# AltiumSchematicSheet.net
KiCad netlist of a schematic drawn in Altium Designer
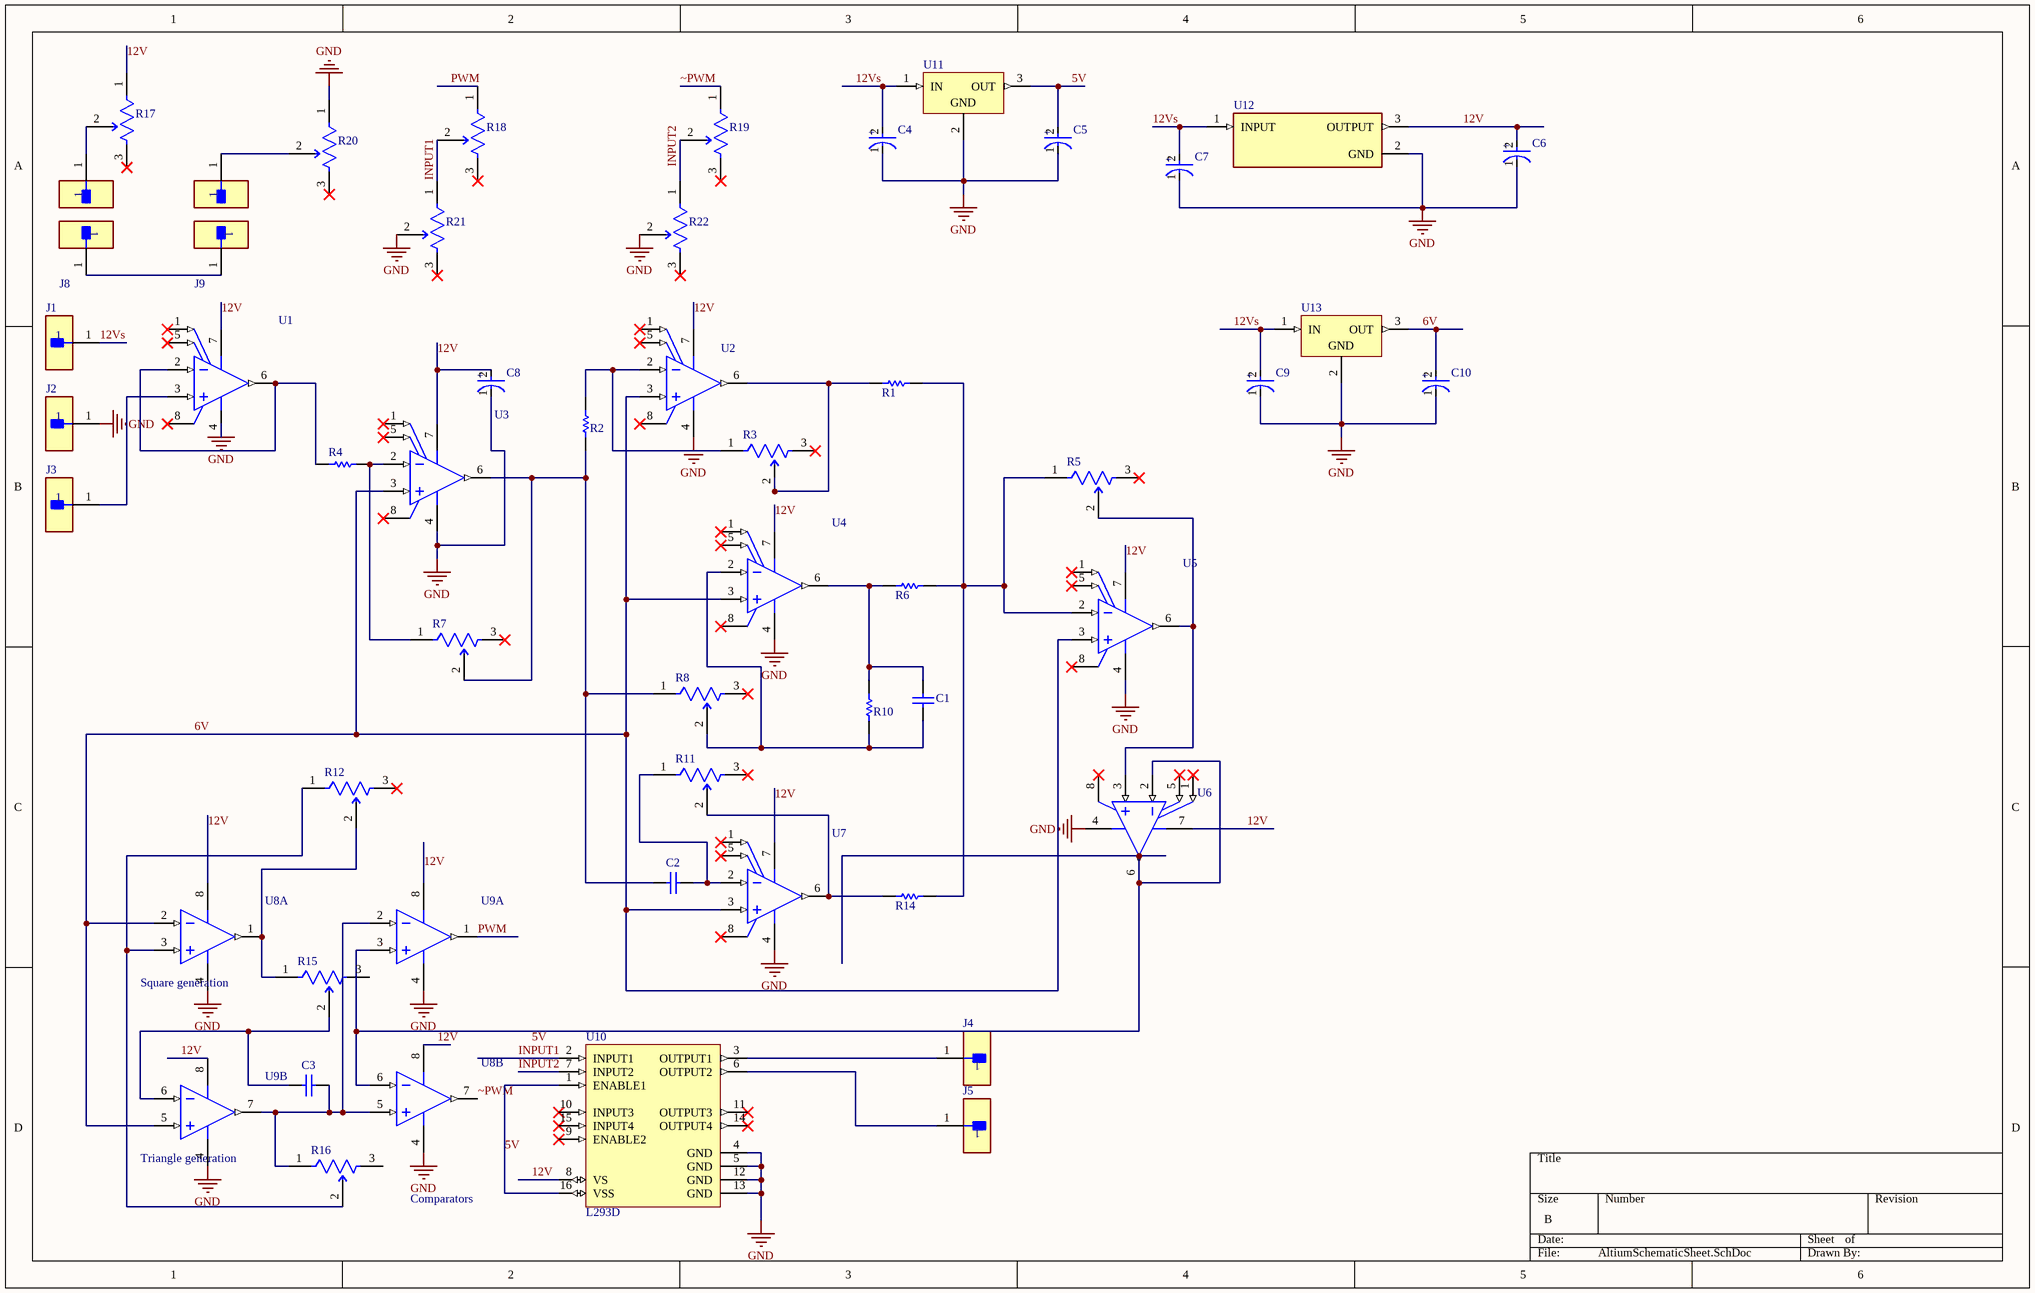
[diagram p0: AltiumSchematicSheet.SchDoc]

(export (version "E")
  (design (tool "Eeschema 10.0.6"))
  (components
    (comp (ref "C1")
      (value "C330C105M5U5TA")
      (footprint "KEMT-C330C105M5U5TA")
      (description "Ceramic Capacitor, 1 uF, +/- 20%, 50 V, -10 to 85 degC, 2-Pin THD, RoHS, Bulk")
      (fields (field (name "TOLERANCE") "±20%") (field (name "MANUFACTURER") "Kemet"))
      (libsource (lib "Altium Content Vault") (part "CAP-NP-2"))
    )
    (comp (ref "C2")
      (value "C330C105M5U5TA")
      (footprint "KEMT-C330C105M5U5TA")
      (description "Ceramic Capacitor, 1 uF, +/- 20%, 50 V, -10 to 85 degC, 2-Pin THD, RoHS, Bulk")
      (fields (field (name "TOLERANCE") "±20%") (field (name "MANUFACTURER") "Kemet"))
      (libsource (lib "Altium Content Vault") (part "CAP-NP-2"))
    )
    (comp (ref "C3")
      (value "C330C105M5U5TA")
      (footprint "KEMT-C330C105M5U5TA")
      (description "Ceramic Capacitor, 1 uF, +/- 20%, 50 V, -10 to 85 degC, 2-Pin THD, RoHS, Bulk")
      (fields (field (name "TOLERANCE") "±20%") (field (name "MANUFACTURER") "Kemet"))
      (libsource (lib "Altium Content Vault") (part "CAP-NP-2"))
    )
    (comp (ref "C4")
      (value "EEUFK1C472L")
      (footprint "FP-RAD-TH-D_12_5_0_5-L_40-MFG")
      (description "Aluminum Electrolytic Capacitors (Radial Lead Type) AEC-Q200 Qualified 4700uF ±20% 16V")
      (fields (field (name "VOLTAGE") "16V") (field (name "TOLERANCE") "20%"))
      (libsource (lib "Altium Content Vault") (part "203bc49f2ac43e59fd269a8c329ed05"))
    )
    (comp (ref "C5")
      (value "EEUFK1C472L")
      (footprint "FP-RAD-TH-D_12_5_0_5-L_40-MFG")
      (description "Aluminum Electrolytic Capacitors (Radial Lead Type) AEC-Q200 Qualified 4700uF ±20% 16V")
      (fields (field (name "VOLTAGE") "16V") (field (name "TOLERANCE") "20%"))
      (libsource (lib "Altium Content Vault") (part "203bc49f2ac43e59fd269a8c329ed05"))
    )
    (comp (ref "C6")
      (value "EEUFK1C472L")
      (footprint "FP-RAD-TH-D_12_5_0_5-L_40-MFG")
      (description "Aluminum Electrolytic Capacitors (Radial Lead Type) AEC-Q200 Qualified 4700uF ±20% 16V")
      (fields (field (name "VOLTAGE") "16V") (field (name "TOLERANCE") "20%"))
      (libsource (lib "Altium Content Vault") (part "203bc49f2ac43e59fd269a8c329ed05"))
    )
    (comp (ref "C7")
      (value "EEUFK1C472L")
      (footprint "FP-RAD-TH-D_12_5_0_5-L_40-MFG")
      (description "Aluminum Electrolytic Capacitors (Radial Lead Type) AEC-Q200 Qualified 4700uF ±20% 16V")
      (fields (field (name "VOLTAGE") "16V") (field (name "TOLERANCE") "20%"))
      (libsource (lib "Altium Content Vault") (part "203bc49f2ac43e59fd269a8c329ed05"))
    )
    (comp (ref "C8")
      (value "EEUFK1C472L")
      (footprint "FP-RAD-TH-D_12_5_0_5-L_40-MFG")
      (description "Aluminum Electrolytic Capacitors (Radial Lead Type) AEC-Q200 Qualified 4700uF ±20% 16V")
      (fields (field (name "VOLTAGE") "16V") (field (name "TOLERANCE") "20%"))
      (libsource (lib "Altium Content Vault") (part "203bc49f2ac43e59fd269a8c329ed05"))
    )
    (comp (ref "C9")
      (value "EEUFK1C472L")
      (footprint "FP-RAD-TH-D_12_5_0_5-L_40-MFG")
      (description "Aluminum Electrolytic Capacitors (Radial Lead Type) AEC-Q200 Qualified 4700uF ±20% 16V")
      (fields (field (name "VOLTAGE") "16V") (field (name "TOLERANCE") "20%"))
      (libsource (lib "Altium Content Vault") (part "203bc49f2ac43e59fd269a8c329ed05"))
    )
    (comp (ref "C10")
      (value "EEUFK1C472L")
      (footprint "FP-RAD-TH-D_12_5_0_5-L_40-MFG")
      (description "Aluminum Electrolytic Capacitors (Radial Lead Type) AEC-Q200 Qualified 4700uF ±20% 16V")
      (fields (field (name "VOLTAGE") "16V") (field (name "TOLERANCE") "20%"))
      (libsource (lib "Altium Content Vault") (part "203bc49f2ac43e59fd269a8c329ed05"))
    )
    (comp (ref "J1")
      (value "PBC01SAAN")
      (footprint "FP-PBC01SAAN-MFG")
      (description "CONN HEADER VERT 1POS")
      (libsource (lib "Altium Content Vault") (part "dd45045ce8184df9e99e12baf3f412c"))
    )
    (comp (ref "J2")
      (value "PBC01SAAN")
      (footprint "FP-PBC01SAAN-MFG")
      (description "CONN HEADER VERT 1POS")
      (libsource (lib "Altium Content Vault") (part "dd45045ce8184df9e99e12baf3f412c"))
    )
    (comp (ref "J3")
      (value "PBC01SAAN")
      (footprint "FP-PBC01SAAN-MFG")
      (description "CONN HEADER VERT 1POS")
      (libsource (lib "Altium Content Vault") (part "dd45045ce8184df9e99e12baf3f412c"))
    )
    (comp (ref "J4")
      (value "PBC01SAAN")
      (footprint "FP-PBC01SAAN-MFG")
      (description "CONN HEADER VERT 1POS")
      (libsource (lib "") (part "dd45045ce8184df9e99e12baf3f412c_2"))
    )
    (comp (ref "J5")
      (value "PBC01SAAN")
      (footprint "FP-PBC01SAAN-MFG")
      (description "CONN HEADER VERT 1POS")
      (libsource (lib "") (part "dd45045ce8184df9e99e12baf3f412c_2"))
    )
    (comp (ref "J6")
      (value "PBC01SAAN")
      (footprint "FP-PBC01SAAN-MFG")
      (description "CONN HEADER VERT 1POS")
      (libsource (lib "") (part "dd45045ce8184df9e99e12baf3f412c_1"))
    )
    (comp (ref "J7")
      (value "PBC01SAAN")
      (footprint "FP-PBC01SAAN-MFG")
      (description "CONN HEADER VERT 1POS")
      (libsource (lib "") (part "dd45045ce8184df9e99e12baf3f412c_1"))
    )
    (comp (ref "J8")
      (value "PBC01SAAN")
      (footprint "FP-PBC01SAAN-MFG")
      (description "CONN HEADER VERT 1POS")
      (libsource (lib "") (part "dd45045ce8184df9e99e12baf3f412c_3"))
    )
    (comp (ref "J9")
      (value "PBC01SAAN")
      (footprint "FP-PBC01SAAN-MFG")
      (description "CONN HEADER VERT 1POS")
      (libsource (lib "") (part "dd45045ce8184df9e99e12baf3f412c_3"))
    )
    (comp (ref "R1")
      (value "MFR-25FBF52-47K5")
      (footprint "RESA60-630X240")
      (description "Axial Resistor, 47.5 KOhm, +/- 1%, 0.25 W, -55 to 155 degC, 2-Pin THD, RoHS, Bulk")
      (fields (field (name "TOLERANCE") "20%"))
      (libsource (lib "Altium Content Vault") (part "RES-2"))
    )
    (comp (ref "R2")
      (value "MFR-25FBF52-47K5")
      (footprint "RESA60-630X240")
      (description "Axial Resistor, 47.5 KOhm, +/- 1%, 0.25 W, -55 to 155 degC, 2-Pin THD, RoHS, Bulk")
      (fields (field (name "TOLERANCE") "20%"))
      (libsource (lib "Altium Content Vault") (part "RES-2"))
    )
    (comp (ref "R3")
      (value "3296W-1-501LF")
      (footprint "FP-3296W-MFG")
      (description "TRIMMER 500 OHM 0.5W PC PIN TOP")
      (fields (field (name "TOLERANCE") "10%"))
      (libsource (lib "Altium Content Vault") (part "2dcfd2547301a7d3209a5e99acfd772"))
    )
    (comp (ref "R4")
      (value "MFR-25FBF52-47K5")
      (footprint "RESA60-630X240")
      (description "Axial Resistor, 47.5 KOhm, +/- 1%, 0.25 W, -55 to 155 degC, 2-Pin THD, RoHS, Bulk")
      (fields (field (name "TOLERANCE") "20%"))
      (libsource (lib "Altium Content Vault") (part "RES-2"))
    )
    (comp (ref "R5")
      (value "3296W-1-501LF")
      (footprint "FP-3296W-MFG")
      (description "TRIMMER 500 OHM 0.5W PC PIN TOP")
      (fields (field (name "TOLERANCE") "10%"))
      (libsource (lib "Altium Content Vault") (part "2dcfd2547301a7d3209a5e99acfd772"))
    )
    (comp (ref "R6")
      (value "MFR-25FBF52-47K5")
      (footprint "RESA60-630X240")
      (description "Axial Resistor, 47.5 KOhm, +/- 1%, 0.25 W, -55 to 155 degC, 2-Pin THD, RoHS, Bulk")
      (fields (field (name "TOLERANCE") "20%"))
      (libsource (lib "Altium Content Vault") (part "RES-2"))
    )
    (comp (ref "R7")
      (value "3296W-1-501LF")
      (footprint "FP-3296W-MFG")
      (description "TRIMMER 500 OHM 0.5W PC PIN TOP")
      (fields (field (name "TOLERANCE") "10%"))
      (libsource (lib "Altium Content Vault") (part "2dcfd2547301a7d3209a5e99acfd772"))
    )
    (comp (ref "R8")
      (value "3296W-1-501LF")
      (footprint "FP-3296W-MFG")
      (description "TRIMMER 500 OHM 0.5W PC PIN TOP")
      (fields (field (name "TOLERANCE") "10%"))
      (libsource (lib "Altium Content Vault") (part "2dcfd2547301a7d3209a5e99acfd772"))
    )
    (comp (ref "R10")
      (value "MFR-25FBF52-47K5")
      (footprint "RESA60-630X240")
      (description "Axial Resistor, 47.5 KOhm, +/- 1%, 0.25 W, -55 to 155 degC, 2-Pin THD, RoHS, Bulk")
      (fields (field (name "TOLERANCE") "20%"))
      (libsource (lib "Altium Content Vault") (part "RES-2"))
    )
    (comp (ref "R11")
      (value "3296W-1-501LF")
      (footprint "FP-3296W-MFG")
      (description "TRIMMER 500 OHM 0.5W PC PIN TOP")
      (fields (field (name "TOLERANCE") "10%"))
      (libsource (lib "Altium Content Vault") (part "2dcfd2547301a7d3209a5e99acfd772"))
    )
    (comp (ref "R12")
      (value "3296W-1-501LF")
      (footprint "FP-3296W-MFG")
      (description "TRIMMER 500 OHM 0.5W PC PIN TOP")
      (fields (field (name "TOLERANCE") "10%"))
      (libsource (lib "Altium Content Vault") (part "2dcfd2547301a7d3209a5e99acfd772"))
    )
    (comp (ref "R14")
      (value "MFR-25FBF52-47K5")
      (footprint "RESA60-630X240")
      (description "Axial Resistor, 47.5 KOhm, +/- 1%, 0.25 W, -55 to 155 degC, 2-Pin THD, RoHS, Bulk")
      (fields (field (name "TOLERANCE") "20%"))
      (libsource (lib "Altium Content Vault") (part "RES-2"))
    )
    (comp (ref "R15")
      (value "3296W-1-501LF")
      (footprint "FP-3296W-MFG")
      (description "TRIMMER 500 OHM 0.5W PC PIN TOP")
      (fields (field (name "TOLERANCE") "10%"))
      (libsource (lib "Altium Content Vault") (part "2dcfd2547301a7d3209a5e99acfd772"))
    )
    (comp (ref "R16")
      (value "3296W-1-501LF")
      (footprint "FP-3296W-MFG")
      (description "TRIMMER 500 OHM 0.5W PC PIN TOP")
      (fields (field (name "TOLERANCE") "10%"))
      (libsource (lib "Altium Content Vault") (part "2dcfd2547301a7d3209a5e99acfd772"))
    )
    (comp (ref "R17")
      (value "3296W-1-501LF")
      (footprint "FP-3296W-MFG")
      (description "TRIMMER 500 OHM 0.5W PC PIN TOP")
      (fields (field (name "TOLERANCE") "10%"))
      (libsource (lib "Altium Content Vault") (part "2dcfd2547301a7d3209a5e99acfd772"))
    )
    (comp (ref "R18")
      (value "3296W-1-501LF")
      (footprint "FP-3296W-MFG")
      (description "TRIMMER 500 OHM 0.5W PC PIN TOP")
      (fields (field (name "TOLERANCE") "10%"))
      (libsource (lib "Altium Content Vault") (part "2dcfd2547301a7d3209a5e99acfd772"))
    )
    (comp (ref "R19")
      (value "3296W-1-501LF")
      (footprint "FP-3296W-MFG")
      (description "TRIMMER 500 OHM 0.5W PC PIN TOP")
      (fields (field (name "TOLERANCE") "10%"))
      (libsource (lib "Altium Content Vault") (part "2dcfd2547301a7d3209a5e99acfd772"))
    )
    (comp (ref "R20")
      (value "3296W-1-501LF")
      (footprint "FP-3296W-MFG")
      (description "TRIMMER 500 OHM 0.5W PC PIN TOP")
      (fields (field (name "TOLERANCE") "10%"))
      (libsource (lib "Altium Content Vault") (part "2dcfd2547301a7d3209a5e99acfd772"))
    )
    (comp (ref "R21")
      (value "3296W-1-501LF")
      (footprint "FP-3296W-MFG")
      (description "TRIMMER 500 OHM 0.5W PC PIN TOP")
      (fields (field (name "TOLERANCE") "10%"))
      (libsource (lib "Altium Content Vault") (part "2dcfd2547301a7d3209a5e99acfd772"))
    )
    (comp (ref "R22")
      (value "3296W-1-501LF")
      (footprint "FP-3296W-MFG")
      (description "TRIMMER 500 OHM 0.5W PC PIN TOP")
      (fields (field (name "TOLERANCE") "10%"))
      (libsource (lib "Altium Content Vault") (part "2dcfd2547301a7d3209a5e99acfd772"))
    )
    (comp (ref "U1")
      (value "UA741CP")
      (footprint "P0008A")
      (description "General-Purpose Operational Amplifier, 7 to 36 V, 0 to 70 degC, 8-pin DIP (P8), Pb-Free (RoHS)")
      (fields (field (name "MANUFACTURER") "Texas Instruments"))
      (libsource (lib "Altium Content Vault") (part "TI-AMP-S5-2-8"))
    )
    (comp (ref "U2")
      (value "UA741CP")
      (footprint "P0008A")
      (description "General-Purpose Operational Amplifier, 7 to 36 V, 0 to 70 degC, 8-pin DIP (P8), Pb-Free (RoHS)")
      (fields (field (name "MANUFACTURER") "Texas Instruments"))
      (libsource (lib "Altium Content Vault") (part "TI-AMP-S5-2-8"))
    )
    (comp (ref "U3")
      (value "UA741CP")
      (footprint "P0008A")
      (description "General-Purpose Operational Amplifier, 7 to 36 V, 0 to 70 degC, 8-pin DIP (P8), Pb-Free (RoHS)")
      (fields (field (name "MANUFACTURER") "Texas Instruments"))
      (libsource (lib "Altium Content Vault") (part "TI-AMP-S5-2-8"))
    )
    (comp (ref "U4")
      (value "UA741CP")
      (footprint "P0008A")
      (description "General-Purpose Operational Amplifier, 7 to 36 V, 0 to 70 degC, 8-pin DIP (P8), Pb-Free (RoHS)")
      (fields (field (name "MANUFACTURER") "Texas Instruments"))
      (libsource (lib "Altium Content Vault") (part "TI-AMP-S5-2-8"))
    )
    (comp (ref "U5")
      (value "UA741CP")
      (footprint "P0008A")
      (description "General-Purpose Operational Amplifier, 7 to 36 V, 0 to 70 degC, 8-pin DIP (P8), Pb-Free (RoHS)")
      (fields (field (name "MANUFACTURER") "Texas Instruments"))
      (libsource (lib "Altium Content Vault") (part "TI-AMP-S5-2-8"))
    )
    (comp (ref "U6")
      (value "UA741CP")
      (footprint "P0008A")
      (description "General-Purpose Operational Amplifier, 7 to 36 V, 0 to 70 degC, 8-pin DIP (P8), Pb-Free (RoHS)")
      (fields (field (name "MANUFACTURER") "Texas Instruments"))
      (libsource (lib "Altium Content Vault") (part "TI-AMP-S5-2-8"))
    )
    (comp (ref "U7")
      (value "UA741CP")
      (footprint "P0008A")
      (description "General-Purpose Operational Amplifier, 7 to 36 V, 0 to 70 degC, 8-pin DIP (P8), Pb-Free (RoHS)")
      (fields (field (name "MANUFACTURER") "Texas Instruments"))
      (libsource (lib "Altium Content Vault") (part "TI-AMP-S5-2-8"))
    )
    (comp (ref "U8")
      (value "TL072CP")
      (footprint "P0008A")
      (fields (field (name "MANUFACTURER") "Texas Instruments"))
      (libsource (lib "Altium Content Vault") (part "TI-AMP-D6-2-8_D"))
    )
    (comp (ref "U9")
      (value "TL072CP")
      (footprint "P0008A")
      (fields (field (name "MANUFACTURER") "Texas Instruments"))
      (libsource (lib "Altium Content Vault") (part "TI-AMP-D6-2-8_D"))
    )
    (comp (ref "U10")
      (value "L293D")
      (footprint "STM-L293D-16")
      (description "Push-Pull Four Channel Driver with Diode, 4.5 to 36 V, -40 to 150 degC, 16-Pin PDIP, RoHS, Tube")
      (fields (field (name "MANUFACTURER") "STMicroelectronics"))
      (libsource (lib "Altium Content Vault") (part "STM-L293D-16"))
    )
    (comp (ref "U11")
      (value "LM7805CT")
      (footprint "FAIR-TO-220-3")
      (description "Positive Voltage Regulator, 5 V, 1 A, -40 to 125 degC, 3-Pin TO-220, RoHS, Tube")
      (fields (field (name "MANUFACTURER") "FairchildSemiconductor"))
      (libsource (lib "Altium Content Vault") (part "FAIR-LM7805CT-TO220-3"))
    )
    (comp (ref "U12")
      (value "LM7812CT")
      (footprint "FP-TO220B03-MFG")
      (description "IC REG LINEAR 12V 1A TO220-3")
      (fields
        (field (name "OCTOPART") "https://octopart.com/lm7812ct-on+semiconductor-14383031")
        (field (name "OBSOLETE PART") "true")
      )
      (libsource (lib "Altium Content Vault") (part "6207a8f1a6b4db326a9e0a8a99b4969"))
    )
    (comp (ref "U13")
      (value "LM7805CT")
      (footprint "FAIR-TO-220-3")
      (description "Positive Voltage Regulator, 5 V, 1 A, -40 to 125 degC, 3-Pin TO-220, RoHS, Tube")
      (fields (field (name "MANUFACTURER") "FairchildSemiconductor"))
      (libsource (lib "Altium Content Vault") (part "FAIR-LM7805CT-TO220-3"))
    )
  )
  (nets
    (net (code "1") (name "/5V") (class "Default")
      (node (ref "C5") (pin "2") (pinfunction "A_2") (pintype "passive"))
      (node (ref "U10") (pin "1") (pinfunction "ENABLE1_1") (pintype "input"))
      (node (ref "U10") (pin "16") (pinfunction "VSS_16") (pintype "bidirectional"))
      (node (ref "U11") (pin "3") (pinfunction "OUT_3") (pintype "output"))
    )
    (net (code "2") (name "/6V") (class "Default")
      (node (ref "C10") (pin "2") (pinfunction "A_2") (pintype "passive"))
      (node (ref "U13") (pin "3") (pinfunction "OUT_3") (pintype "output"))
      (node (ref "U2") (pin "3") (pinfunction "IN+_3") (pintype "input"))
      (node (ref "U3") (pin "3") (pinfunction "IN+_3") (pintype "input"))
      (node (ref "U4") (pin "3") (pinfunction "IN+_3") (pintype "input"))
      (node (ref "U5") (pin "3") (pinfunction "IN+_3") (pintype "input"))
      (node (ref "U7") (pin "3") (pinfunction "IN+_3") (pintype "input"))
      (node (ref "U8") (pin "2") (pinfunction "IN1-_2") (pintype "input"))
      (node (ref "U9") (pin "5") (pinfunction "IN2+_5") (pintype "input"))
    )
    (net (code "3") (name "/12V") (class "Default")
      (node (ref "C6") (pin "2") (pinfunction "A_2") (pintype "passive"))
      (node (ref "C8") (pin "2") (pinfunction "A_2") (pintype "passive"))
      (node (ref "R17") (pin "1") (pinfunction "CCW_1") (pintype "passive"))
      (node (ref "U1") (pin "7") (pinfunction "VCC+_7") (pintype "power_in"))
      (node (ref "U10") (pin "8") (pinfunction "VS_8") (pintype "bidirectional"))
      (node (ref "U12") (pin "3") (pinfunction "OUTPUT_3") (pintype "output"))
      (node (ref "U2") (pin "7") (pinfunction "VCC+_7") (pintype "power_in"))
      (node (ref "U3") (pin "7") (pinfunction "VCC+_7") (pintype "power_in"))
      (node (ref "U4") (pin "7") (pinfunction "VCC+_7") (pintype "power_in"))
      (node (ref "U5") (pin "7") (pinfunction "VCC+_7") (pintype "power_in"))
      (node (ref "U6") (pin "7") (pinfunction "VCC+_7") (pintype "power_in"))
      (node (ref "U7") (pin "7") (pinfunction "VCC+_7") (pintype "power_in"))
      (node (ref "U8") (pin "8") (pinfunction "VCC+_8") (pintype "power_in"))
      (node (ref "U9") (pin "8") (pinfunction "VCC+_8") (pintype "power_in"))
    )
    (net (code "4") (name "/12Vs") (class "Default")
      (node (ref "C4") (pin "2") (pinfunction "A_2") (pintype "passive"))
      (node (ref "C7") (pin "2") (pinfunction "A_2") (pintype "passive"))
      (node (ref "C9") (pin "2") (pinfunction "A_2") (pintype "passive"))
      (node (ref "J1") (pin "1") (pinfunction "1_1") (pintype "passive"))
      (node (ref "U11") (pin "1") (pinfunction "IN_1") (pintype "input"))
      (node (ref "U12") (pin "1") (pinfunction "INPUT_1") (pintype "input"))
      (node (ref "U13") (pin "1") (pinfunction "IN_1") (pintype "input"))
    )
    (net (code "5") (name "/INPUT1") (class "Default")
      (node (ref "R18") (pin "2") (pinfunction "WIPER_2") (pintype "passive"))
      (node (ref "R21") (pin "1") (pinfunction "CCW_1") (pintype "passive"))
      (node (ref "U10") (pin "2") (pinfunction "INPUT1_2") (pintype "input"))
    )
    (net (code "6") (name "/INPUT2") (class "Default")
      (node (ref "R19") (pin "2") (pinfunction "WIPER_2") (pintype "passive"))
      (node (ref "R22") (pin "1") (pinfunction "CCW_1") (pintype "passive"))
      (node (ref "U10") (pin "7") (pinfunction "INPUT2_7") (pintype "input"))
    )
    (net (code "7") (name "/PWM") (class "Default")
      (node (ref "R18") (pin "1") (pinfunction "CCW_1") (pintype "passive"))
      (node (ref "U9") (pin "1") (pinfunction "OUT1_1") (pintype "output"))
    )
    (net (code "8") (name "/~PWM") (class "Default")
      (node (ref "R19") (pin "1") (pinfunction "CCW_1") (pintype "passive"))
      (node (ref "U8") (pin "7") (pinfunction "OUT2_7") (pintype "output"))
    )
    (net (code "9") (name "GND") (class "Default")
      (node (ref "C10") (pin "1") (pinfunction "C_1") (pintype "passive"))
      (node (ref "C4") (pin "1") (pinfunction "C_1") (pintype "passive"))
      (node (ref "C5") (pin "1") (pinfunction "C_1") (pintype "passive"))
      (node (ref "C6") (pin "1") (pinfunction "C_1") (pintype "passive"))
      (node (ref "C7") (pin "1") (pinfunction "C_1") (pintype "passive"))
      (node (ref "C8") (pin "1") (pinfunction "C_1") (pintype "passive"))
      (node (ref "C9") (pin "1") (pinfunction "C_1") (pintype "passive"))
      (node (ref "J2") (pin "1") (pinfunction "1_1") (pintype "passive"))
      (node (ref "R20") (pin "1") (pinfunction "CCW_1") (pintype "passive"))
      (node (ref "R21") (pin "2") (pinfunction "WIPER_2") (pintype "passive"))
      (node (ref "R22") (pin "2") (pinfunction "WIPER_2") (pintype "passive"))
      (node (ref "U1") (pin "4") (pinfunction "VCC-_4") (pintype "power_in"))
      (node (ref "U10") (pin "12") (pinfunction "GND_12") (pintype "power_in"))
      (node (ref "U10") (pin "13") (pinfunction "GND_13") (pintype "power_in"))
      (node (ref "U10") (pin "4") (pinfunction "GND_4") (pintype "power_in"))
      (node (ref "U10") (pin "5") (pinfunction "GND_5") (pintype "power_in"))
      (node (ref "U11") (pin "2") (pinfunction "GND_2") (pintype "power_in"))
      (node (ref "U12") (pin "2") (pinfunction "GND_2") (pintype "power_in"))
      (node (ref "U13") (pin "2") (pinfunction "GND_2") (pintype "power_in"))
      (node (ref "U2") (pin "4") (pinfunction "VCC-_4") (pintype "power_in"))
      (node (ref "U3") (pin "4") (pinfunction "VCC-_4") (pintype "power_in"))
      (node (ref "U4") (pin "4") (pinfunction "VCC-_4") (pintype "power_in"))
      (node (ref "U5") (pin "4") (pinfunction "VCC-_4") (pintype "power_in"))
      (node (ref "U6") (pin "4") (pinfunction "VCC-_4") (pintype "power_in"))
      (node (ref "U7") (pin "4") (pinfunction "VCC-_4") (pintype "power_in"))
      (node (ref "U8") (pin "4") (pinfunction "VCC-_4") (pintype "power_in"))
      (node (ref "U9") (pin "4") (pinfunction "VCC-_4") (pintype "power_in"))
    )
    (net (code "10") (name "Net-(J8-Pad1)") (class "Default")
      (node (ref "J8") (pin "1") (pinfunction "1_1") (pintype "passive"))
      (node (ref "J9") (pin "1") (pinfunction "1_1") (pintype "passive"))
    )
    (net (code "11") (name "Net-(R3-CCW)") (class "Default")
      (node (ref "R2") (pin "2") (pinfunction "2_2") (pintype "passive"))
      (node (ref "R3") (pin "1") (pinfunction "CCW_1") (pintype "passive"))
      (node (ref "U2") (pin "2") (pinfunction "IN-_2") (pintype "input"))
    )
    (net (code "12") (name "Net-(R3-WIPER)") (class "Default")
      (node (ref "R1") (pin "2") (pinfunction "2_2") (pintype "passive"))
      (node (ref "R3") (pin "2") (pinfunction "WIPER_2") (pintype "passive"))
      (node (ref "U2") (pin "6") (pinfunction "OUT_6") (pintype "output"))
    )
    (net (code "13") (name "Net-(R5-CCW)") (class "Default")
      (node (ref "R1") (pin "1") (pinfunction "1_1") (pintype "passive"))
      (node (ref "R14") (pin "1") (pinfunction "1_1") (pintype "passive"))
      (node (ref "R5") (pin "1") (pinfunction "CCW_1") (pintype "passive"))
      (node (ref "R6") (pin "1") (pinfunction "1_1") (pintype "passive"))
      (node (ref "U5") (pin "2") (pinfunction "IN-_2") (pintype "input"))
    )
    (net (code "14") (name "Net-(R5-WIPER)") (class "Default")
      (node (ref "R5") (pin "2") (pinfunction "WIPER_2") (pintype "passive"))
      (node (ref "U5") (pin "6") (pinfunction "OUT_6") (pintype "output"))
      (node (ref "U6") (pin "3") (pinfunction "IN+_3") (pintype "input"))
    )
    (net (code "15") (name "Net-(R7-CCW)") (class "Default")
      (node (ref "R4") (pin "2") (pinfunction "2_2") (pintype "passive"))
      (node (ref "R7") (pin "1") (pinfunction "CCW_1") (pintype "passive"))
      (node (ref "U3") (pin "2") (pinfunction "IN-_2") (pintype "input"))
    )
    (net (code "16") (name "Net-(R7-WIPER)") (class "Default")
      (node (ref "C2") (pin "2") (pinfunction "2_2") (pintype "passive"))
      (node (ref "R2") (pin "1") (pinfunction "1_1") (pintype "passive"))
      (node (ref "R7") (pin "2") (pinfunction "WIPER_2") (pintype "passive"))
      (node (ref "R8") (pin "1") (pinfunction "CCW_1") (pintype "passive"))
      (node (ref "U3") (pin "6") (pinfunction "OUT_6") (pintype "output"))
    )
    (net (code "17") (name "Net-(R8-WIPER)") (class "Default")
      (node (ref "C1") (pin "1") (pinfunction "1_1") (pintype "passive"))
      (node (ref "R10") (pin "1") (pinfunction "1_1") (pintype "passive"))
      (node (ref "R8") (pin "2") (pinfunction "WIPER_2") (pintype "passive"))
      (node (ref "U4") (pin "2") (pinfunction "IN-_2") (pintype "input"))
    )
    (net (code "18") (name "Net-(R11-CCW)") (class "Default")
      (node (ref "C2") (pin "1") (pinfunction "1_1") (pintype "passive"))
      (node (ref "R11") (pin "1") (pinfunction "CCW_1") (pintype "passive"))
      (node (ref "U7") (pin "2") (pinfunction "IN-_2") (pintype "input"))
    )
    (net (code "19") (name "Net-(R11-WIPER)") (class "Default")
      (node (ref "R11") (pin "2") (pinfunction "WIPER_2") (pintype "passive"))
      (node (ref "R14") (pin "2") (pinfunction "2_2") (pintype "passive"))
      (node (ref "U7") (pin "6") (pinfunction "OUT_6") (pintype "output"))
    )
    (net (code "20") (name "Net-(R12-CCW)") (class "Default")
      (node (ref "R12") (pin "1") (pinfunction "CCW_1") (pintype "passive"))
      (node (ref "R16") (pin "2") (pinfunction "WIPER_2") (pintype "passive"))
      (node (ref "U8") (pin "3") (pinfunction "IN1+_3") (pintype "input"))
    )
    (net (code "21") (name "Net-(R12-WIPER)") (class "Default")
      (node (ref "R12") (pin "2") (pinfunction "WIPER_2") (pintype "passive"))
      (node (ref "R15") (pin "1") (pinfunction "CCW_1") (pintype "passive"))
      (node (ref "U8") (pin "1") (pinfunction "OUT1_1") (pintype "output"))
    )
    (net (code "22") (name "Net-(R15-WIPER)") (class "Default")
      (node (ref "C3") (pin "2") (pinfunction "2_2") (pintype "passive"))
      (node (ref "R15") (pin "2") (pinfunction "WIPER_2") (pintype "passive"))
      (node (ref "U9") (pin "6") (pinfunction "IN2-_6") (pintype "input"))
    )
    (net (code "23") (name "Net-(R16-CCW)") (class "Default")
      (node (ref "C3") (pin "1") (pinfunction "1_1") (pintype "passive"))
      (node (ref "R16") (pin "1") (pinfunction "CCW_1") (pintype "passive"))
      (node (ref "U8") (pin "5") (pinfunction "IN2+_5") (pintype "input"))
      (node (ref "U9") (pin "2") (pinfunction "IN1-_2") (pintype "input"))
      (node (ref "U9") (pin "7") (pinfunction "OUT2_7") (pintype "output"))
    )
    (net (code "24") (name "Net-(R17-WIPER)") (class "Default")
      (node (ref "J6") (pin "1") (pinfunction "1_1") (pintype "passive"))
      (node (ref "R17") (pin "2") (pinfunction "WIPER_2") (pintype "passive"))
    )
    (net (code "25") (name "Net-(R20-WIPER)") (class "Default")
      (node (ref "J7") (pin "1") (pinfunction "1_1") (pintype "passive"))
      (node (ref "R20") (pin "2") (pinfunction "WIPER_2") (pintype "passive"))
    )
    (net (code "26") (name "Net-(U1-IN+)") (class "Default")
      (node (ref "J3") (pin "1") (pinfunction "1_1") (pintype "passive"))
      (node (ref "U1") (pin "3") (pinfunction "IN+_3") (pintype "input"))
    )
    (net (code "27") (name "Net-(U1-IN-)") (class "Default")
      (node (ref "R4") (pin "1") (pinfunction "1_1") (pintype "passive"))
      (node (ref "U1") (pin "2") (pinfunction "IN-_2") (pintype "input"))
      (node (ref "U1") (pin "6") (pinfunction "OUT_6") (pintype "output"))
    )
    (net (code "28") (name "Net-(U4-OUT)") (class "Default")
      (node (ref "C1") (pin "2") (pinfunction "2_2") (pintype "passive"))
      (node (ref "R10") (pin "2") (pinfunction "2_2") (pintype "passive"))
      (node (ref "R6") (pin "2") (pinfunction "2_2") (pintype "passive"))
      (node (ref "U4") (pin "6") (pinfunction "OUT_6") (pintype "output"))
    )
    (net (code "29") (name "Net-(U6-IN-)") (class "Default")
      (node (ref "U6") (pin "2") (pinfunction "IN-_2") (pintype "input"))
      (node (ref "U6") (pin "6") (pinfunction "OUT_6") (pintype "output"))
      (node (ref "U8") (pin "6") (pinfunction "IN2-_6") (pintype "input"))
      (node (ref "U9") (pin "3") (pinfunction "IN1+_3") (pintype "input"))
    )
    (net (code "30") (name "Net-(U10-OUTPUT1)") (class "Default")
      (node (ref "J4") (pin "1") (pinfunction "1_1") (pintype "passive"))
      (node (ref "U10") (pin "3") (pinfunction "OUTPUT1_3") (pintype "output"))
    )
    (net (code "31") (name "Net-(U10-OUTPUT2)") (class "Default")
      (node (ref "J5") (pin "1") (pinfunction "1_1") (pintype "passive"))
      (node (ref "U10") (pin "6") (pinfunction "OUTPUT2_6") (pintype "output"))
    )
    (net (code "32") (name "unconnected-(R3-CW-Pad3)") (class "Default")
      (node (ref "R3") (pin "3") (pinfunction "CW_3") (pintype "passive+no_connect"))
    )
    (net (code "33") (name "unconnected-(R5-CW-Pad3)") (class "Default")
      (node (ref "R5") (pin "3") (pinfunction "CW_3") (pintype "passive+no_connect"))
    )
    (net (code "34") (name "unconnected-(R7-CW-Pad3)") (class "Default")
      (node (ref "R7") (pin "3") (pinfunction "CW_3") (pintype "passive+no_connect"))
    )
    (net (code "35") (name "unconnected-(R8-CW-Pad3)") (class "Default")
      (node (ref "R8") (pin "3") (pinfunction "CW_3") (pintype "passive+no_connect"))
    )
    (net (code "36") (name "unconnected-(R11-CW-Pad3)") (class "Default")
      (node (ref "R11") (pin "3") (pinfunction "CW_3") (pintype "passive+no_connect"))
    )
    (net (code "37") (name "unconnected-(R12-CW-Pad3)") (class "Default")
      (node (ref "R12") (pin "3") (pinfunction "CW_3") (pintype "passive+no_connect"))
    )
    (net (code "38") (name "unconnected-(R15-CW-Pad3)") (class "Default")
      (node (ref "R15") (pin "3") (pinfunction "CW_3") (pintype "passive"))
    )
    (net (code "39") (name "unconnected-(R16-CW-Pad3)") (class "Default")
      (node (ref "R16") (pin "3") (pinfunction "CW_3") (pintype "passive"))
    )
    (net (code "40") (name "unconnected-(R17-CW-Pad3)") (class "Default")
      (node (ref "R17") (pin "3") (pinfunction "CW_3") (pintype "passive+no_connect"))
    )
    (net (code "41") (name "unconnected-(R18-CW-Pad3)") (class "Default")
      (node (ref "R18") (pin "3") (pinfunction "CW_3") (pintype "passive+no_connect"))
    )
    (net (code "42") (name "unconnected-(R19-CW-Pad3)") (class "Default")
      (node (ref "R19") (pin "3") (pinfunction "CW_3") (pintype "passive+no_connect"))
    )
    (net (code "43") (name "unconnected-(R20-CW-Pad3)") (class "Default")
      (node (ref "R20") (pin "3") (pinfunction "CW_3") (pintype "passive+no_connect"))
    )
    (net (code "44") (name "unconnected-(R21-CW-Pad3)") (class "Default")
      (node (ref "R21") (pin "3") (pinfunction "CW_3") (pintype "passive+no_connect"))
    )
    (net (code "45") (name "unconnected-(R22-CW-Pad3)") (class "Default")
      (node (ref "R22") (pin "3") (pinfunction "CW_3") (pintype "passive+no_connect"))
    )
    (net (code "46") (name "unconnected-(U1-NC-Pad8)") (class "Default")
      (node (ref "U1") (pin "8") (pinfunction "NC_8") (pintype "passive+no_connect"))
    )
    (net (code "47") (name "unconnected-(U1-OFFSET_N1-Pad1)") (class "Default")
      (node (ref "U1") (pin "1") (pinfunction "OFFSET_N1_1") (pintype "input+no_connect"))
    )
    (net (code "48") (name "unconnected-(U1-OFFSET_N2-Pad5)") (class "Default")
      (node (ref "U1") (pin "5") (pinfunction "OFFSET_N2_5") (pintype "input+no_connect"))
    )
    (net (code "49") (name "unconnected-(U2-NC-Pad8)") (class "Default")
      (node (ref "U2") (pin "8") (pinfunction "NC_8") (pintype "passive+no_connect"))
    )
    (net (code "50") (name "unconnected-(U2-OFFSET_N1-Pad1)") (class "Default")
      (node (ref "U2") (pin "1") (pinfunction "OFFSET_N1_1") (pintype "input+no_connect"))
    )
    (net (code "51") (name "unconnected-(U2-OFFSET_N2-Pad5)") (class "Default")
      (node (ref "U2") (pin "5") (pinfunction "OFFSET_N2_5") (pintype "input+no_connect"))
    )
    (net (code "52") (name "unconnected-(U3-NC-Pad8)") (class "Default")
      (node (ref "U3") (pin "8") (pinfunction "NC_8") (pintype "passive+no_connect"))
    )
    (net (code "53") (name "unconnected-(U3-OFFSET_N1-Pad1)") (class "Default")
      (node (ref "U3") (pin "1") (pinfunction "OFFSET_N1_1") (pintype "input+no_connect"))
    )
    (net (code "54") (name "unconnected-(U3-OFFSET_N2-Pad5)") (class "Default")
      (node (ref "U3") (pin "5") (pinfunction "OFFSET_N2_5") (pintype "input+no_connect"))
    )
    (net (code "55") (name "unconnected-(U4-NC-Pad8)") (class "Default")
      (node (ref "U4") (pin "8") (pinfunction "NC_8") (pintype "passive+no_connect"))
    )
    (net (code "56") (name "unconnected-(U4-OFFSET_N1-Pad1)") (class "Default")
      (node (ref "U4") (pin "1") (pinfunction "OFFSET_N1_1") (pintype "input+no_connect"))
    )
    (net (code "57") (name "unconnected-(U4-OFFSET_N2-Pad5)") (class "Default")
      (node (ref "U4") (pin "5") (pinfunction "OFFSET_N2_5") (pintype "input+no_connect"))
    )
    (net (code "58") (name "unconnected-(U5-NC-Pad8)") (class "Default")
      (node (ref "U5") (pin "8") (pinfunction "NC_8") (pintype "passive+no_connect"))
    )
    (net (code "59") (name "unconnected-(U5-OFFSET_N1-Pad1)") (class "Default")
      (node (ref "U5") (pin "1") (pinfunction "OFFSET_N1_1") (pintype "input+no_connect"))
    )
    (net (code "60") (name "unconnected-(U5-OFFSET_N2-Pad5)") (class "Default")
      (node (ref "U5") (pin "5") (pinfunction "OFFSET_N2_5") (pintype "input+no_connect"))
    )
    (net (code "61") (name "unconnected-(U6-NC-Pad8)") (class "Default")
      (node (ref "U6") (pin "8") (pinfunction "NC_8") (pintype "passive+no_connect"))
    )
    (net (code "62") (name "unconnected-(U6-OFFSET_N1-Pad1)") (class "Default")
      (node (ref "U6") (pin "1") (pinfunction "OFFSET_N1_1") (pintype "input+no_connect"))
    )
    (net (code "63") (name "unconnected-(U6-OFFSET_N2-Pad5)") (class "Default")
      (node (ref "U6") (pin "5") (pinfunction "OFFSET_N2_5") (pintype "input+no_connect"))
    )
    (net (code "64") (name "unconnected-(U7-NC-Pad8)") (class "Default")
      (node (ref "U7") (pin "8") (pinfunction "NC_8") (pintype "passive+no_connect"))
    )
    (net (code "65") (name "unconnected-(U7-OFFSET_N1-Pad1)") (class "Default")
      (node (ref "U7") (pin "1") (pinfunction "OFFSET_N1_1") (pintype "input+no_connect"))
    )
    (net (code "66") (name "unconnected-(U7-OFFSET_N2-Pad5)") (class "Default")
      (node (ref "U7") (pin "5") (pinfunction "OFFSET_N2_5") (pintype "input+no_connect"))
    )
    (net (code "67") (name "unconnected-(U10-ENABLE2-Pad9)") (class "Default")
      (node (ref "U10") (pin "9") (pinfunction "ENABLE2_9") (pintype "input+no_connect"))
    )
    (net (code "68") (name "unconnected-(U10-INPUT3-Pad10)") (class "Default")
      (node (ref "U10") (pin "10") (pinfunction "INPUT3_10") (pintype "input+no_connect"))
    )
    (net (code "69") (name "unconnected-(U10-INPUT4-Pad15)") (class "Default")
      (node (ref "U10") (pin "15") (pinfunction "INPUT4_15") (pintype "input+no_connect"))
    )
    (net (code "70") (name "unconnected-(U10-OUTPUT3-Pad11)") (class "Default")
      (node (ref "U10") (pin "11") (pinfunction "OUTPUT3_11") (pintype "output+no_connect"))
    )
    (net (code "71") (name "unconnected-(U10-OUTPUT4-Pad14)") (class "Default")
      (node (ref "U10") (pin "14") (pinfunction "OUTPUT4_14") (pintype "output+no_connect"))
    )
  )
)
